# VOEDING.net
KiCad netlist of a schematic drawn in Altium Designer
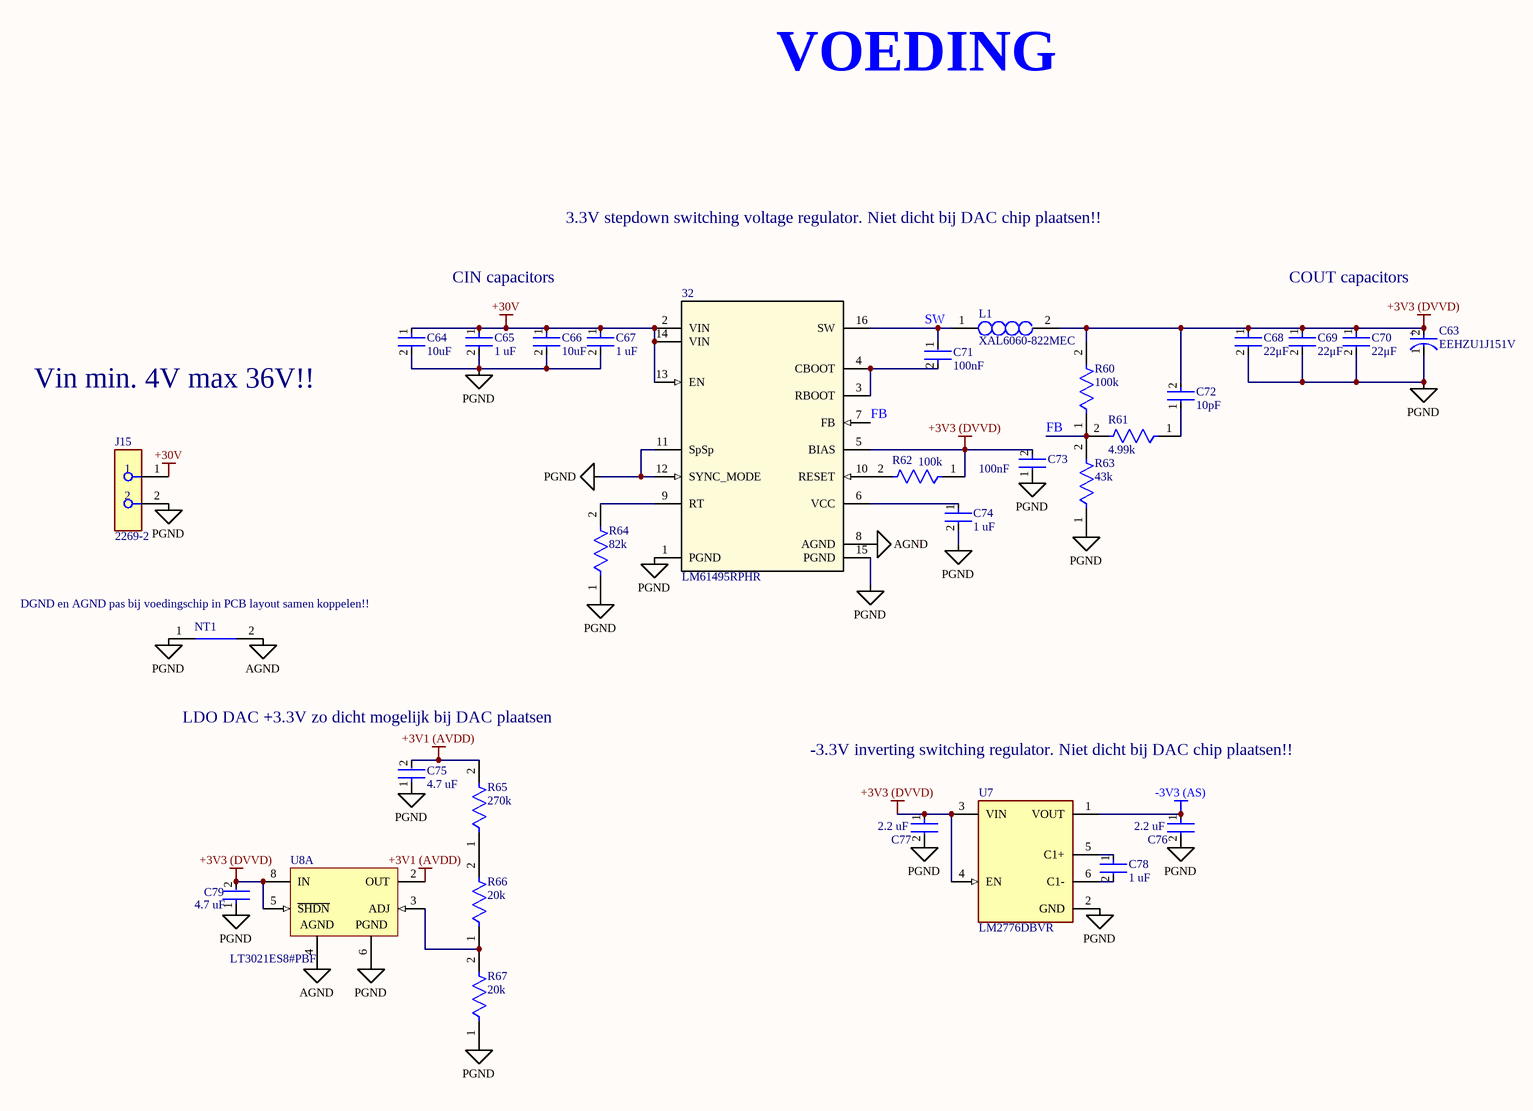
[diagram p0: VOEDING.SchDoc]

(export (version "E")
  (design (tool "Eeschema 10.0.6"))
  (components
    (comp (ref "32")
      (value "LM61495RPHR")
      (footprint "RPH0016A")
      (description "No Description Available")
      (libsource (lib "LM61495RPHR") (part "LM61495RPHR"))
    )
    (comp (ref "C63")
      (value "EEHZU1J151V")
      (footprint "FP-EEH-G16-V-MFG")
      (description "Aluminum Hybrid Polymer Capacitors 150uF 20% 63V Life 4000Hours AEC-Q200 RADIAL SMT")
      (libsource (lib "Altium Content Vault") (part "203bc49f2ac43e59fd269a8c329ed05"))
    )
    (comp (ref "C64")
      (value "10uF")
      (footprint "FP-GRM32-MFG")
      (description "CAP CER 10UF 50V X7R 1210")
      (fields (field (name "TOLERANCE") "10%") (field (name "MANUFACTURER PART NUMBER") "GRM32ER71H106KA12L"))
      (libsource (lib "Altium Content Vault") (part "11868f565c42a9108669ba33697ecf6"))
    )
    (comp (ref "C65")
      (value "1 uF")
      (footprint "FP-C0603C-CF-MFG")
      (description "CAP CER 1 UF 50V 5% X7R 0603")
      (fields (field (name "TOLERANCE") "0.05") (field (name "MANUFACTURER PART NUMBER") "C0603C104J5RACTU"))
      (libsource (lib "Altium Content Vault") (part "b4654b650e69147ec39a6b967a45e02"))
    )
    (comp (ref "C66")
      (value "10uF")
      (footprint "FP-GRM32-MFG")
      (description "CAP CER 10UF 50V X7R 1210")
      (fields (field (name "TOLERANCE") "10%") (field (name "MANUFACTURER PART NUMBER") "GRM32ER71H106KA12L"))
      (libsource (lib "Altium Content Vault") (part "11868f565c42a9108669ba33697ecf6"))
    )
    (comp (ref "C67")
      (value "1 uF")
      (footprint "FP-C0603C-CF-MFG")
      (description "CAP CER 1 UF 50V 5% X7R 0603")
      (fields (field (name "TOLERANCE") "0.05") (field (name "MANUFACTURER PART NUMBER") "C0603C104J5RACTU"))
      (libsource (lib "Altium Content Vault") (part "b4654b650e69147ec39a6b967a45e02"))
    )
    (comp (ref "C68")
      (value "22μF")
      (footprint "FP-C2012-125-0_2-MFG")
      (description "Multilayer Ceramic Capacitors 22μF ±20% 10V X5R SMD 0805")
      (fields (field (name "TOLERANCE") "20%"))
      (libsource (lib "Altium Content Vault") (part "b4654b650e69147ec39a6b967a45e02"))
    )
    (comp (ref "C69")
      (value "22μF")
      (footprint "FP-C2012-125-0_2-MFG")
      (description "Multilayer Ceramic Capacitors 22μF ±20% 10V X5R SMD 0805")
      (fields (field (name "TOLERANCE") "20%"))
      (libsource (lib "Altium Content Vault") (part "b4654b650e69147ec39a6b967a45e02"))
    )
    (comp (ref "C70")
      (value "22μF")
      (footprint "FP-C2012-125-0_2-MFG")
      (description "Multilayer Ceramic Capacitors 22μF ±20% 10V X5R SMD 0805")
      (fields (field (name "TOLERANCE") "20%"))
      (libsource (lib "Altium Content Vault") (part "b4654b650e69147ec39a6b967a45e02"))
    )
    (comp (ref "C71")
      (value "100nF")
      (footprint "FP-GRM15-MFG")
      (description "CAP CER 0.1UF 16V X7R 0402")
      (fields (field (name "MANUFACTURER PART NUMBER") "GRM155R71C104KA88D") (field (name "TOLERANCE") "10%"))
      (libsource (lib "Altium Content Vault") (part "236180d848d6139a670b325ea6854c9"))
    )
    (comp (ref "C72")
      (value "10pF")
      (footprint "FP-GRM15-MFG")
      (description "CAP CER 10pF 16V X7R 0402")
      (fields (field (name "MANUFACTURER PART NUMBER") "GRM155R71C104KA88D") (field (name "TOLERANCE") "10%"))
      (libsource (lib "Altium Content Vault") (part "236180d848d6139a670b325ea6854c9"))
    )
    (comp (ref "C73")
      (value "100nF")
      (footprint "FP-GRM15-MFG")
      (description "CAP CER 0.1UF 16V X7R 0402")
      (fields (field (name "MANUFACTURER PART NUMBER") "GRM155R71C104KA88D") (field (name "TOLERANCE") "10%"))
      (libsource (lib "Altium Content Vault") (part "236180d848d6139a670b325ea6854c9"))
    )
    (comp (ref "C74")
      (value "1 uF")
      (footprint "FP-C0603C-CF-MFG")
      (description "CAP CER 1 UF 50V 5% X7R 0603")
      (fields (field (name "TOLERANCE") "0.05") (field (name "MANUFACTURER PART NUMBER") "C0603C104J5RACTU"))
      (libsource (lib "Altium Content Vault") (part "b4654b650e69147ec39a6b967a45e02"))
    )
    (comp (ref "C75")
      (value "4.7 uF")
      (footprint "FP-C0603C-CF-MFG")
      (description "CAP CER 4.7 UF 50V 5% X7R 0603")
      (fields (field (name "TOLERANCE") "0.05") (field (name "MANUFACTURER PART NUMBER") "C0603C104J5RACTU"))
      (libsource (lib "Altium Content Vault") (part "b4654b650e69147ec39a6b967a45e02"))
    )
    (comp (ref "C76")
      (value "2.2 uF")
      (footprint "FP-C0603C-CF-MFG")
      (description "CAP CER 2.2 UF 50V 5% X7R 0603")
      (fields (field (name "TOLERANCE") "0.05") (field (name "MANUFACTURER PART NUMBER") "C0603C104J5RACTU"))
      (libsource (lib "Altium Content Vault") (part "b4654b650e69147ec39a6b967a45e02"))
    )
    (comp (ref "C77")
      (value "2.2 uF")
      (footprint "FP-C0603C-CF-MFG")
      (description "CAP CER 2.2 UF 50V 5% X7R 0603")
      (fields (field (name "TOLERANCE") "0.05") (field (name "MANUFACTURER PART NUMBER") "C0603C104J5RACTU"))
      (libsource (lib "Altium Content Vault") (part "b4654b650e69147ec39a6b967a45e02"))
    )
    (comp (ref "C78")
      (value "1 uF")
      (footprint "FP-C0603C-CF-MFG")
      (description "CAP CER 1 UF 50V 5% X7R 0603")
      (fields (field (name "TOLERANCE") "0.05") (field (name "MANUFACTURER PART NUMBER") "C0603C104J5RACTU"))
      (libsource (lib "Altium Content Vault") (part "b4654b650e69147ec39a6b967a45e02"))
    )
    (comp (ref "C79")
      (value "4.7 uF")
      (footprint "FP-C0603C-CF-MFG")
      (description "CAP CER 4.7 UF 50V 5% X7R 0603")
      (fields (field (name "TOLERANCE") "0.05") (field (name "MANUFACTURER PART NUMBER") "C0603C104J5RACTU"))
      (libsource (lib "Altium Content Vault") (part "b4654b650e69147ec39a6b967a45e02"))
    )
    (comp (ref "J15")
      (value "2269-2")
      (footprint "FP-2269-2-MFG")
      (description "CONN DBL BANANA JACK TURRET")
      (libsource (lib "Altium Content Vault") (part "3ddab50f66188bb7952c54a1b76274c"))
    )
    (comp (ref "L1")
      (value "XAL6060-822MEC")
      (footprint "SamacSys:XAL6060822MEC")
      (description "8.2 uH Inductor")
      (fields (field (name "MOUSER PART NUMBER") "994-XAL6060-822MEC"))
      (libsource (lib "*") (part "XAL6060-822MEC"))
    )
    (comp (ref "NT1")
      (value "NT (AGND en PGND)")
      (footprint "NET_TIE_SMD_")
      (description "NET TIE SMD")
      (libsource (lib "Schlib1") (part "NET_TIE_SMD"))
    )
    (comp (ref "R60")
      (value "100k")
      (footprint "FP-CRCW0402-C-e3-MFG")
      (description "RES 100K OHM 1% 1/16W 0402")
      (fields (field (name "TOLERANCE") "1%"))
      (libsource (lib "Altium Content Vault") (part "1029c3af85768c4190bb7ad29bc67b5"))
    )
    (comp (ref "R61")
      (value "4.99k")
      (footprint "FP-CRCW0402-e3-MFG")
      (description "RES Thick Film, 4.99kΩ, 1%, 0.063W, 100ppm/°C, 0402")
      (fields (field (name "TOLERANCE") "1%"))
      (libsource (lib "Altium Content Vault") (part "1029c3af85768c4190bb7ad29bc67b5"))
    )
    (comp (ref "R62")
      (value "100k")
      (footprint "FP-CRCW0402-C-e3-MFG")
      (description "RES 100K OHM 1% 1/16W 0402")
      (fields (field (name "TOLERANCE") "1%"))
      (libsource (lib "Altium Content Vault") (part "1029c3af85768c4190bb7ad29bc67b5"))
    )
    (comp (ref "R63")
      (value "43k")
      (footprint "FP-CRCW0402-C-e3-MFG")
      (description "RES 43k OHM 1% 1/16W 0402")
      (fields (field (name "TOLERANCE") "1%"))
      (libsource (lib "Altium Content Vault") (part "1029c3af85768c4190bb7ad29bc67b5"))
    )
    (comp (ref "R64")
      (value "82k")
      (footprint "FP-CRCW0402-C-e3-MFG")
      (description "RES 100K OHM 1% 1/16W 0402")
      (fields (field (name "TOLERANCE") "1%"))
      (libsource (lib "Altium Content Vault") (part "1029c3af85768c4190bb7ad29bc67b5"))
    )
    (comp (ref "R65")
      (value "270k")
      (footprint "FP-CRCW0402-C-e3-MFG")
      (description "RES 270K OHM 1% 1/16W 0402")
      (fields (field (name "TOLERANCE") "1%"))
      (libsource (lib "Altium Content Vault") (part "1029c3af85768c4190bb7ad29bc67b5"))
    )
    (comp (ref "R66")
      (value "20k")
      (footprint "FP-CRCW0402-C-e3-MFG")
      (description "RES 20K OHM 1% 1/16W 0402")
      (fields (field (name "TOLERANCE") "1%"))
      (libsource (lib "Altium Content Vault") (part "1029c3af85768c4190bb7ad29bc67b5"))
    )
    (comp (ref "R67")
      (value "20k")
      (footprint "FP-CRCW0402-C-e3-MFG")
      (description "RES 20K OHM 1% 1/16W 0402")
      (fields (field (name "TOLERANCE") "1%"))
      (libsource (lib "Altium Content Vault") (part "1029c3af85768c4190bb7ad29bc67b5"))
    )
    (comp (ref "U7")
      (value "LM2776DBVR")
      (footprint "FP-DBV0006A-MFG")
      (description "IC REG CHARGE PUMP INV SOT23")
      (fields
        (field (name "MANUFACTURER") "Texas Instruments")
        (field (name "OCTOPART") "https://octopart.com/lm2776dbvr-texas+instruments-58839919")
      )
      (libsource (lib "Altium Content Vault") (part "aa1f6f8daf1b38e6829d08268534e6c"))
    )
    (comp (ref "U8")
      (value "LT3021ES8#PBF")
      (footprint "LT-S8-8_L")
      (fields (field (name "MANUFACTURER") "Linear Technology"))
      (libsource (lib "Altium Content Vault") (part "LT-LT3021-S8-8_B"))
    )
  )
  (nets
    (net (code "1") (name "+3V1 (AVDD)") (class "Default")
      (node (ref "C75") (pin "2") (pinfunction "2_2") (pintype "passive"))
      (node (ref "R65") (pin "2") (pinfunction "2_2") (pintype "passive"))
      (node (ref "U8") (pin "2") (pinfunction "OUT_2") (pintype "power_in"))
    )
    (net (code "2") (name "+3V3 (DVVD)") (class "Default")
      (node (ref "32") (pin "5") (pinfunction "BIAS_5") (pintype "passive"))
      (node (ref "C63") (pin "2") (pinfunction "A_2") (pintype "passive"))
      (node (ref "C68") (pin "1") (pinfunction "1_1") (pintype "passive"))
      (node (ref "C69") (pin "1") (pinfunction "1_1") (pintype "passive"))
      (node (ref "C70") (pin "1") (pinfunction "1_1") (pintype "passive"))
      (node (ref "C72") (pin "2") (pinfunction "2_2") (pintype "passive"))
      (node (ref "C73") (pin "2") (pinfunction "2_2") (pintype "passive"))
      (node (ref "C77") (pin "1") (pinfunction "1_1") (pintype "passive"))
      (node (ref "C79") (pin "2") (pinfunction "2_2") (pintype "passive"))
      (node (ref "L1") (pin "2") (pinfunction "2_2") (pintype "passive"))
      (node (ref "R60") (pin "2") (pinfunction "2_2") (pintype "passive"))
      (node (ref "R62") (pin "1") (pinfunction "1_1") (pintype "passive"))
      (node (ref "U7") (pin "3") (pinfunction "VIN_3") (pintype "power_in"))
      (node (ref "U7") (pin "4") (pinfunction "EN_4") (pintype "input"))
      (node (ref "U8") (pin "5") (pinfunction "~{SHDN}_5") (pintype "input"))
      (node (ref "U8") (pin "8") (pinfunction "IN_8") (pintype "power_in"))
    )
    (net (code "3") (name "+30V") (class "Default")
      (node (ref "32") (pin "13") (pinfunction "EN_13") (pintype "input"))
      (node (ref "32") (pin "14") (pinfunction "VIN_14") (pintype "power_in"))
      (node (ref "32") (pin "2") (pinfunction "VIN_2") (pintype "power_in"))
      (node (ref "C64") (pin "1") (pinfunction "1_1") (pintype "passive"))
      (node (ref "C65") (pin "1") (pinfunction "1_1") (pintype "passive"))
      (node (ref "C66") (pin "1") (pinfunction "1_1") (pintype "passive"))
      (node (ref "C67") (pin "1") (pinfunction "1_1") (pintype "passive"))
      (node (ref "J15") (pin "1") (pinfunction "1_1") (pintype "passive"))
    )
    (net (code "4") (name "-3V3 (AS)") (class "Default")
      (node (ref "C76") (pin "1") (pinfunction "1_1") (pintype "passive"))
      (node (ref "U7") (pin "1") (pinfunction "VOUT_1") (pintype "power_in"))
    )
    (net (code "5") (name "/FB") (class "Default")
      (node (ref "32") (pin "7") (pinfunction "FB_7") (pintype "input"))
      (node (ref "R60") (pin "1") (pinfunction "1_1") (pintype "passive"))
      (node (ref "R61") (pin "2") (pinfunction "2_2") (pintype "passive"))
      (node (ref "R63") (pin "2") (pinfunction "2_2") (pintype "passive"))
    )
    (net (code "6") (name "/SW") (class "Default")
      (node (ref "32") (pin "16") (pinfunction "SW_16") (pintype "power_in"))
      (node (ref "C71") (pin "1") (pinfunction "1_1") (pintype "passive"))
      (node (ref "L1") (pin "1") (pinfunction "1_1") (pintype "passive"))
    )
    (net (code "7") (name "AGND") (class "Default")
      (node (ref "32") (pin "8") (pinfunction "AGND_8") (pintype "power_in"))
      (node (ref "NT1") (pin "2") (pinfunction "2_2") (pintype "passive"))
      (node (ref "U8") (pin "4") (pinfunction "AGND_4") (pintype "power_in"))
    )
    (net (code "8") (name "Net-(32-CBOOT)") (class "Default")
      (node (ref "32") (pin "3") (pinfunction "RBOOT_3") (pintype "passive"))
      (node (ref "32") (pin "4") (pinfunction "CBOOT_4") (pintype "passive"))
      (node (ref "C71") (pin "2") (pinfunction "2_2") (pintype "passive"))
    )
    (net (code "9") (name "Net-(32-RESET)") (class "Default")
      (node (ref "32") (pin "10") (pinfunction "RESET_10") (pintype "input"))
      (node (ref "R62") (pin "2") (pinfunction "2_2") (pintype "passive"))
    )
    (net (code "10") (name "Net-(32-RT)") (class "Default")
      (node (ref "32") (pin "9") (pinfunction "RT_9") (pintype "passive"))
      (node (ref "R64") (pin "2") (pinfunction "2_2") (pintype "passive"))
    )
    (net (code "11") (name "Net-(32-VCC)") (class "Default")
      (node (ref "32") (pin "6") (pinfunction "VCC_6") (pintype "power_in"))
      (node (ref "C74") (pin "1") (pinfunction "1_1") (pintype "passive"))
    )
    (net (code "12") (name "Net-(C72-Pad1)") (class "Default")
      (node (ref "C72") (pin "1") (pinfunction "1_1") (pintype "passive"))
      (node (ref "R61") (pin "1") (pinfunction "1_1") (pintype "passive"))
    )
    (net (code "13") (name "Net-(R65-Pad1)") (class "Default")
      (node (ref "R65") (pin "1") (pinfunction "1_1") (pintype "passive"))
      (node (ref "R66") (pin "2") (pinfunction "2_2") (pintype "passive"))
    )
    (net (code "14") (name "Net-(U7-C1+)") (class "Default")
      (node (ref "C78") (pin "1") (pinfunction "1_1") (pintype "passive"))
      (node (ref "U7") (pin "5") (pinfunction "C1+_5") (pintype "power_in"))
    )
    (net (code "15") (name "Net-(U7-C1-)") (class "Default")
      (node (ref "C78") (pin "2") (pinfunction "2_2") (pintype "passive"))
      (node (ref "U7") (pin "6") (pinfunction "C1-_6") (pintype "power_in"))
    )
    (net (code "16") (name "Net-(U8A-ADJ)") (class "Default")
      (node (ref "R66") (pin "1") (pinfunction "1_1") (pintype "passive"))
      (node (ref "R67") (pin "2") (pinfunction "2_2") (pintype "passive"))
      (node (ref "U8") (pin "3") (pinfunction "ADJ_3") (pintype "input"))
    )
    (net (code "17") (name "PGND") (class "Default")
      (node (ref "32") (pin "1") (pinfunction "PGND_1") (pintype "power_in"))
      (node (ref "32") (pin "11") (pinfunction "SpSp_11") (pintype "passive"))
      (node (ref "32") (pin "12") (pinfunction "SYNC_MODE_12") (pintype "input"))
      (node (ref "32") (pin "15") (pinfunction "PGND_15") (pintype "power_in"))
      (node (ref "C63") (pin "1") (pinfunction "C_1") (pintype "passive"))
      (node (ref "C64") (pin "2") (pinfunction "2_2") (pintype "passive"))
      (node (ref "C65") (pin "2") (pinfunction "2_2") (pintype "passive"))
      (node (ref "C66") (pin "2") (pinfunction "2_2") (pintype "passive"))
      (node (ref "C67") (pin "2") (pinfunction "2_2") (pintype "passive"))
      (node (ref "C68") (pin "2") (pinfunction "2_2") (pintype "passive"))
      (node (ref "C69") (pin "2") (pinfunction "2_2") (pintype "passive"))
      (node (ref "C70") (pin "2") (pinfunction "2_2") (pintype "passive"))
      (node (ref "C73") (pin "1") (pinfunction "1_1") (pintype "passive"))
      (node (ref "C74") (pin "2") (pinfunction "2_2") (pintype "passive"))
      (node (ref "C75") (pin "1") (pinfunction "1_1") (pintype "passive"))
      (node (ref "C76") (pin "2") (pinfunction "2_2") (pintype "passive"))
      (node (ref "C77") (pin "2") (pinfunction "2_2") (pintype "passive"))
      (node (ref "C79") (pin "1") (pinfunction "1_1") (pintype "passive"))
      (node (ref "J15") (pin "2") (pinfunction "2_2") (pintype "passive"))
      (node (ref "NT1") (pin "1") (pinfunction "1_1") (pintype "passive"))
      (node (ref "R63") (pin "1") (pinfunction "1_1") (pintype "passive"))
      (node (ref "R64") (pin "1") (pinfunction "1_1") (pintype "passive"))
      (node (ref "R67") (pin "1") (pinfunction "1_1") (pintype "passive"))
      (node (ref "U7") (pin "2") (pinfunction "GND_2") (pintype "power_in"))
      (node (ref "U8") (pin "6") (pinfunction "PGND_6") (pintype "power_in"))
    )
  )
)
